# CTR_CAN.net
KiCad netlist of a schematic drawn in Altium Designer
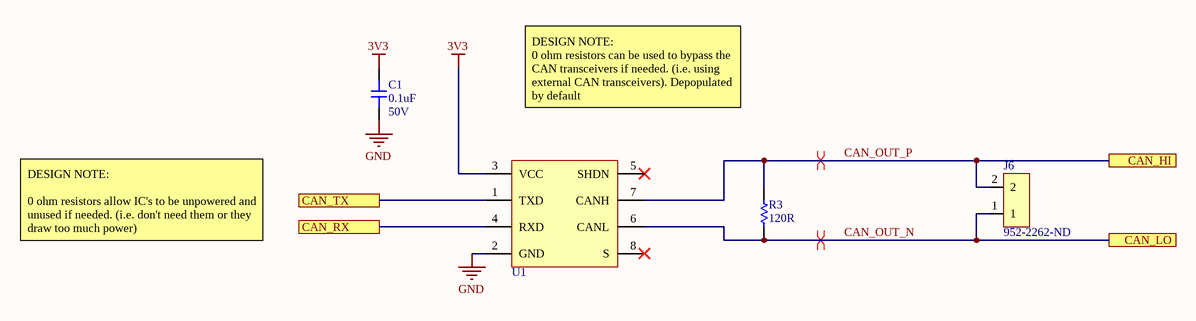
[diagram p0: CTR_CAN.SchDoc]

(export (version "E")
  (design (tool "Eeschema 10.0.6"))
  (components
    (comp (ref "C1")
      (value "0.1uF")
      (footprint "CAP-0805")
      (description "CAP CER 0.1UF 50V Y5V 0805")
      (fields
        (field (name "MANUFACTURER") "KEMET")
        (field (name "MANUFACTURER PART NUMBER") "C0805C104Z5VACTU")
        (field (name "VOLTAGE RATING") "50V")
      )
      (libsource (lib "InverterSCHLib") (part "0805-0.1uF-50V"))
    )
    (comp (ref "J6")
      (value "952-2262-ND")
      (footprint "2PIN_HEADER")
      (description "CONN HEADER VERT 2POS 2.54MM")
      (fields (field (name "MANUFACTURER") "Harwin") (field (name "MANUFACTURER PART NUMBER") "M20-9990246"))
      (libsource (lib "InverterSCHLib") (part "M20-9990246"))
    )
    (comp (ref "R3")
      (value "120R")
      (footprint "RES-0603")
      (description "RES SMD 120 OHM 1% 1/10W 0603")
      (fields
        (field (name "MANUFACTURER") "Yageo")
        (field (name "MANUFACTURER PART NUMBER") "RC0603FR-07120RL")
      )
      (libsource (lib "InverterSCHLib") (part "0603-120R"))
    )
    (comp (ref "U1")
      (value "TCAN332DR")
      (footprint "8-SOIC_MCP2561")
      (description "IC TRANSCEIVER 1/1 8SOIC")
      (fields (field (name "MANUFACTURER") "Texas Instruments"))
      (libsource (lib "InverterSCHLib") (part "TCAN332DR"))
    )
  )
  (nets
    (net (code "1") (name "/CAN_OUT_N") (class "Default")
      (node (ref "J6") (pin "1") (pinfunction "1_1") (pintype "passive"))
      (node (ref "R3") (pin "1") (pinfunction "1_1") (pintype "passive"))
      (node (ref "U1") (pin "6") (pinfunction "CANL_6") (pintype "passive"))
    )
    (net (code "2") (name "/CAN_OUT_P") (class "Default")
      (node (ref "J6") (pin "2") (pinfunction "2_2") (pintype "passive"))
      (node (ref "R3") (pin "2") (pinfunction "2_2") (pintype "passive"))
      (node (ref "U1") (pin "7") (pinfunction "CANH_7") (pintype "passive"))
    )
    (net (code "3") (name "/CAN_RX") (class "Default")
      (node (ref "U1") (pin "4") (pinfunction "RXD_4") (pintype "passive"))
    )
    (net (code "4") (name "/CAN_TX") (class "Default")
      (node (ref "U1") (pin "1") (pinfunction "TXD_1") (pintype "passive"))
    )
    (net (code "5") (name "3V3") (class "Default")
      (node (ref "C1") (pin "2") (pinfunction "2_2") (pintype "passive"))
      (node (ref "U1") (pin "3") (pinfunction "VCC_3") (pintype "passive"))
    )
    (net (code "6") (name "GND") (class "Default")
      (node (ref "C1") (pin "1") (pinfunction "1_1") (pintype "passive"))
      (node (ref "U1") (pin "2") (pinfunction "GND_2") (pintype "passive"))
    )
    (net (code "7") (name "unconnected-(U1-S-Pad8)") (class "Default")
      (node (ref "U1") (pin "8") (pinfunction "S_8") (pintype "passive+no_connect"))
    )
    (net (code "8") (name "unconnected-(U1-SHDN-Pad5)") (class "Default")
      (node (ref "U1") (pin "5") (pinfunction "SHDN_5") (pintype "passive+no_connect"))
    )
  )
)
